# gbg_v01.net
KiCad netlist of a schematic drawn in EAGLE
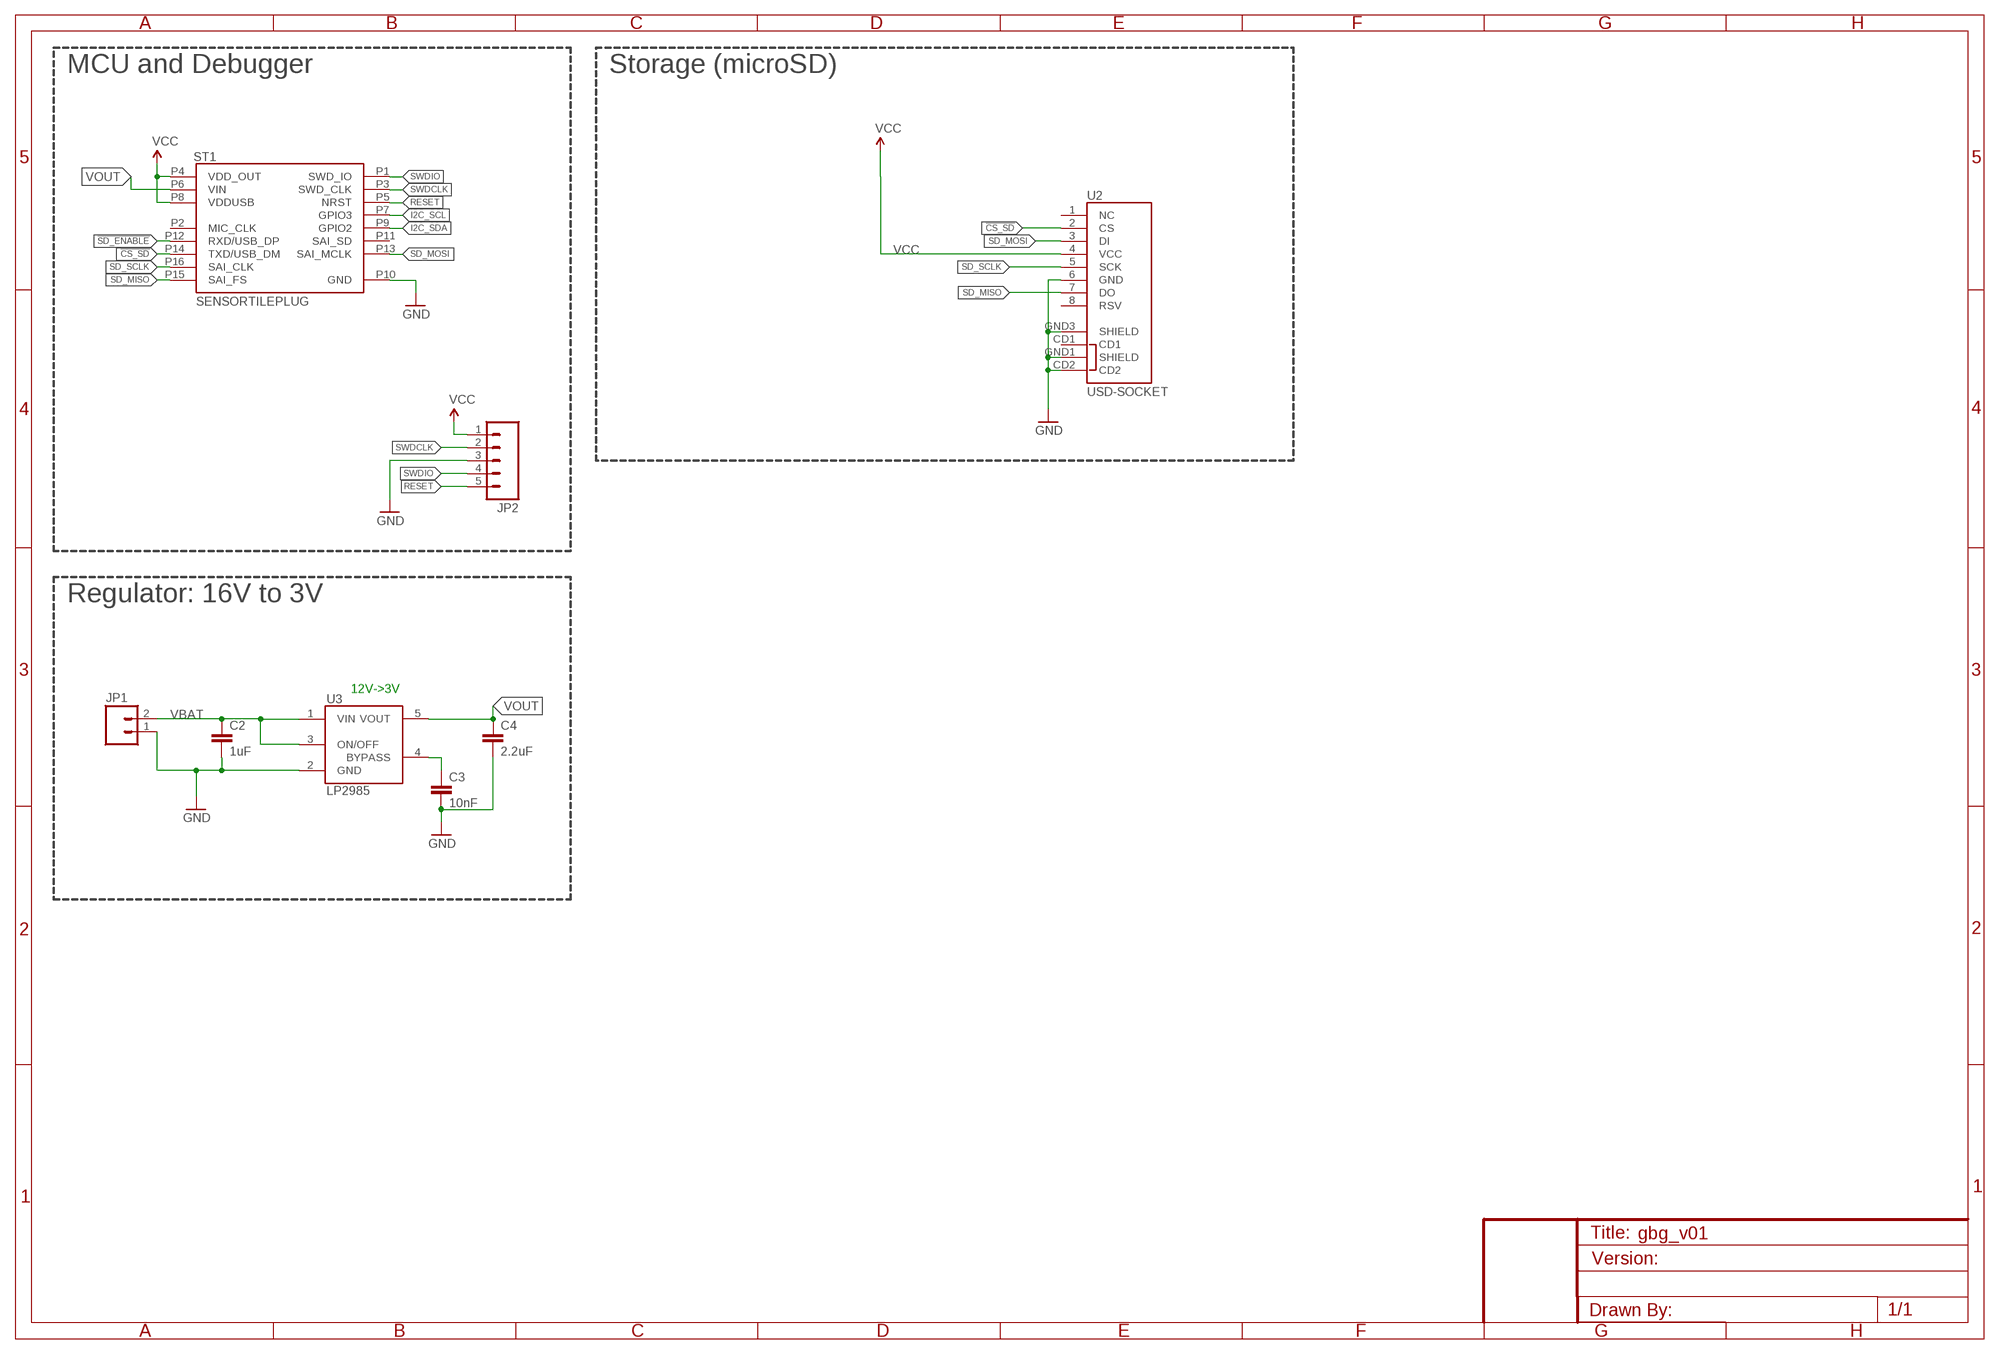
[diagram p0: schematic, sheet 1]

(export (version "E")
  (design (tool "Eeschema 10.0.6"))
  (components
    (comp (ref "C2")
      (value "1uF")
      (footprint "eagle-import:0603")
      (libsource (lib "eagle-import") (part "C-EU0603"))
    )
    (comp (ref "C3")
      (value "10nF")
      (footprint "eagle-import:0603")
      (libsource (lib "eagle-import") (part "C-EU0603"))
    )
    (comp (ref "C4")
      (value "2.2uF")
      (footprint "eagle-import:0603")
      (libsource (lib "eagle-import") (part "C-EU0603"))
    )
    (comp (ref "JP1")
      (value "M025MM")
      (footprint "eagle-import:SCREWTERMINAL-5MM-2")
      (libsource (lib "eagle-import") (part "M025MM"))
    )
    (comp (ref "JP2")
      (value "M05LOCK")
      (footprint "eagle-import:1X05_LOCK")
      (libsource (lib "eagle-import") (part "M05LOCK"))
    )
    (comp (ref "ST1")
      (value "SENSORTILEPLUG")
      (footprint "eagle-import:BM10JC16")
      (libsource (lib "eagle-import") (part "SENSORTILEPLUG"))
    )
    (comp (ref "U2")
      (value "USD-SOCKET")
      (footprint "eagle-import:MICROSD_1_1")
      (libsource (lib "eagle-import") (part "USD-SOCKET"))
    )
    (comp (ref "U3")
      (value "LP2985AIM5-3.3")
      (footprint "eagle-import:SOT25")
      (fields (field (name "MPN") "LP2985-30DBVR  "))
      (libsource (lib "eagle-import") (part "LP2985AIM5-3.3"))
    )
  )
  (nets
    (net (code "1") (name "/VBAT") (class "Default")
      (node (ref "C2") (pin "1") (pinfunction "1_1") (pintype "passive"))
      (node (ref "JP1") (pin "2") (pinfunction "2_2") (pintype "passive"))
      (node (ref "U3") (pin "1") (pinfunction "VIN_1") (pintype "power_in"))
      (node (ref "U3") (pin "3") (pinfunction "ON/OFF_3") (pintype "input"))
    )
    (net (code "2") (name "/~{CS_SD}") (class "Default")
      (node (ref "ST1") (pin "P14") (pinfunction "TXD/USB_DM_P14") (pintype "bidirectional"))
      (node (ref "U2") (pin "2") (pinfunction "CS_2") (pintype "bidirectional"))
    )
    (net (code "3") (name "/~{SD_ENABLE}") (class "Default")
      (node (ref "ST1") (pin "P12") (pinfunction "RXD/USB_DP_P12") (pintype "bidirectional"))
    )
    (net (code "4") (name "GND") (class "Default")
      (node (ref "C2") (pin "2") (pinfunction "2_2") (pintype "passive"))
      (node (ref "C3") (pin "2") (pinfunction "2_2") (pintype "passive"))
      (node (ref "C4") (pin "2") (pinfunction "2_2") (pintype "passive"))
      (node (ref "JP1") (pin "1") (pinfunction "1_1") (pintype "passive"))
      (node (ref "JP2") (pin "3") (pinfunction "3_3") (pintype "passive"))
      (node (ref "ST1") (pin "P10") (pinfunction "GND_P10") (pintype "bidirectional"))
      (node (ref "U2") (pin "6") (pinfunction "GND_6") (pintype "bidirectional"))
      (node (ref "U2") (pin "CD2") (pinfunction "CD2_CD2") (pintype "bidirectional"))
      (node (ref "U2") (pin "GND1") (pinfunction "SHIELD_GND1") (pintype "bidirectional"))
      (node (ref "U2") (pin "GND3") (pinfunction "SHIELD_GND3") (pintype "bidirectional"))
      (node (ref "U3") (pin "2") (pinfunction "GND_2") (pintype "power_in"))
    )
    (net (code "5") (name "I2C_SCL") (class "Default")
      (node (ref "ST1") (pin "P7") (pinfunction "GPIO3_P7") (pintype "bidirectional"))
    )
    (net (code "6") (name "I2C_SDA") (class "Default")
      (node (ref "ST1") (pin "P9") (pinfunction "GPIO2_P9") (pintype "bidirectional"))
    )
    (net (code "7") (name "Net-(U3-BYPASS)") (class "Default")
      (node (ref "C3") (pin "1") (pinfunction "1_1") (pintype "passive"))
      (node (ref "U3") (pin "4") (pinfunction "BYPASS_4") (pintype "power_in"))
    )
    (net (code "8") (name "RESET") (class "Default")
      (node (ref "JP2") (pin "5") (pinfunction "5_5") (pintype "passive"))
      (node (ref "ST1") (pin "P5") (pinfunction "NRST_P5") (pintype "bidirectional"))
    )
    (net (code "9") (name "SD_MISO") (class "Default")
      (node (ref "ST1") (pin "P15") (pinfunction "SAI_FS_P15") (pintype "bidirectional"))
      (node (ref "U2") (pin "7") (pinfunction "DO_7") (pintype "bidirectional"))
    )
    (net (code "10") (name "SD_MOSI") (class "Default")
      (node (ref "ST1") (pin "P13") (pinfunction "SAI_MCLK_P13") (pintype "bidirectional"))
      (node (ref "U2") (pin "3") (pinfunction "DI_3") (pintype "bidirectional"))
    )
    (net (code "11") (name "SD_SCLK") (class "Default")
      (node (ref "ST1") (pin "P16") (pinfunction "SAI_CLK_P16") (pintype "bidirectional"))
      (node (ref "U2") (pin "5") (pinfunction "SCK_5") (pintype "bidirectional"))
    )
    (net (code "12") (name "SWDCLK") (class "Default")
      (node (ref "JP2") (pin "2") (pinfunction "2_2") (pintype "passive"))
      (node (ref "ST1") (pin "P3") (pinfunction "SWD_CLK_P3") (pintype "bidirectional"))
    )
    (net (code "13") (name "SWDIO") (class "Default")
      (node (ref "JP2") (pin "4") (pinfunction "4_4") (pintype "passive"))
      (node (ref "ST1") (pin "P1") (pinfunction "SWD_IO_P1") (pintype "bidirectional"))
    )
    (net (code "14") (name "VCC") (class "Default")
      (node (ref "JP2") (pin "1") (pinfunction "1_1") (pintype "passive"))
      (node (ref "ST1") (pin "P4") (pinfunction "VDD_OUT_P4") (pintype "bidirectional"))
      (node (ref "ST1") (pin "P8") (pinfunction "VDDUSB_P8") (pintype "bidirectional"))
      (node (ref "U2") (pin "4") (pinfunction "VCC_4") (pintype "bidirectional"))
    )
    (net (code "15") (name "VOUT") (class "Default")
      (node (ref "C4") (pin "1") (pinfunction "1_1") (pintype "passive"))
      (node (ref "ST1") (pin "P6") (pinfunction "VIN_P6") (pintype "bidirectional"))
      (node (ref "U3") (pin "5") (pinfunction "VOUT_5") (pintype "power_in"))
    )
    (net (code "16") (name "unconnected-(ST1-MIC_CLK-PadP2)") (class "Default")
      (node (ref "ST1") (pin "P2") (pinfunction "MIC_CLK_P2") (pintype "bidirectional"))
    )
    (net (code "17") (name "unconnected-(ST1-SAI_SD-PadP11)") (class "Default")
      (node (ref "ST1") (pin "P11") (pinfunction "SAI_SD_P11") (pintype "bidirectional"))
    )
    (net (code "18") (name "unconnected-(U2-NC-Pad1)") (class "Default")
      (node (ref "U2") (pin "1") (pinfunction "NC_1") (pintype "bidirectional"))
    )
    (net (code "19") (name "unconnected-(U2-PadCD1)") (class "Default")
      (node (ref "U2") (pin "CD1") (pinfunction "CD1_CD1") (pintype "bidirectional"))
    )
    (net (code "20") (name "unconnected-(U2-RSV-Pad8)") (class "Default")
      (node (ref "U2") (pin "8") (pinfunction "RSV_8") (pintype "bidirectional"))
    )
  )
)
